# linemixer2.net
KiCad netlist of a schematic drawn in EAGLE
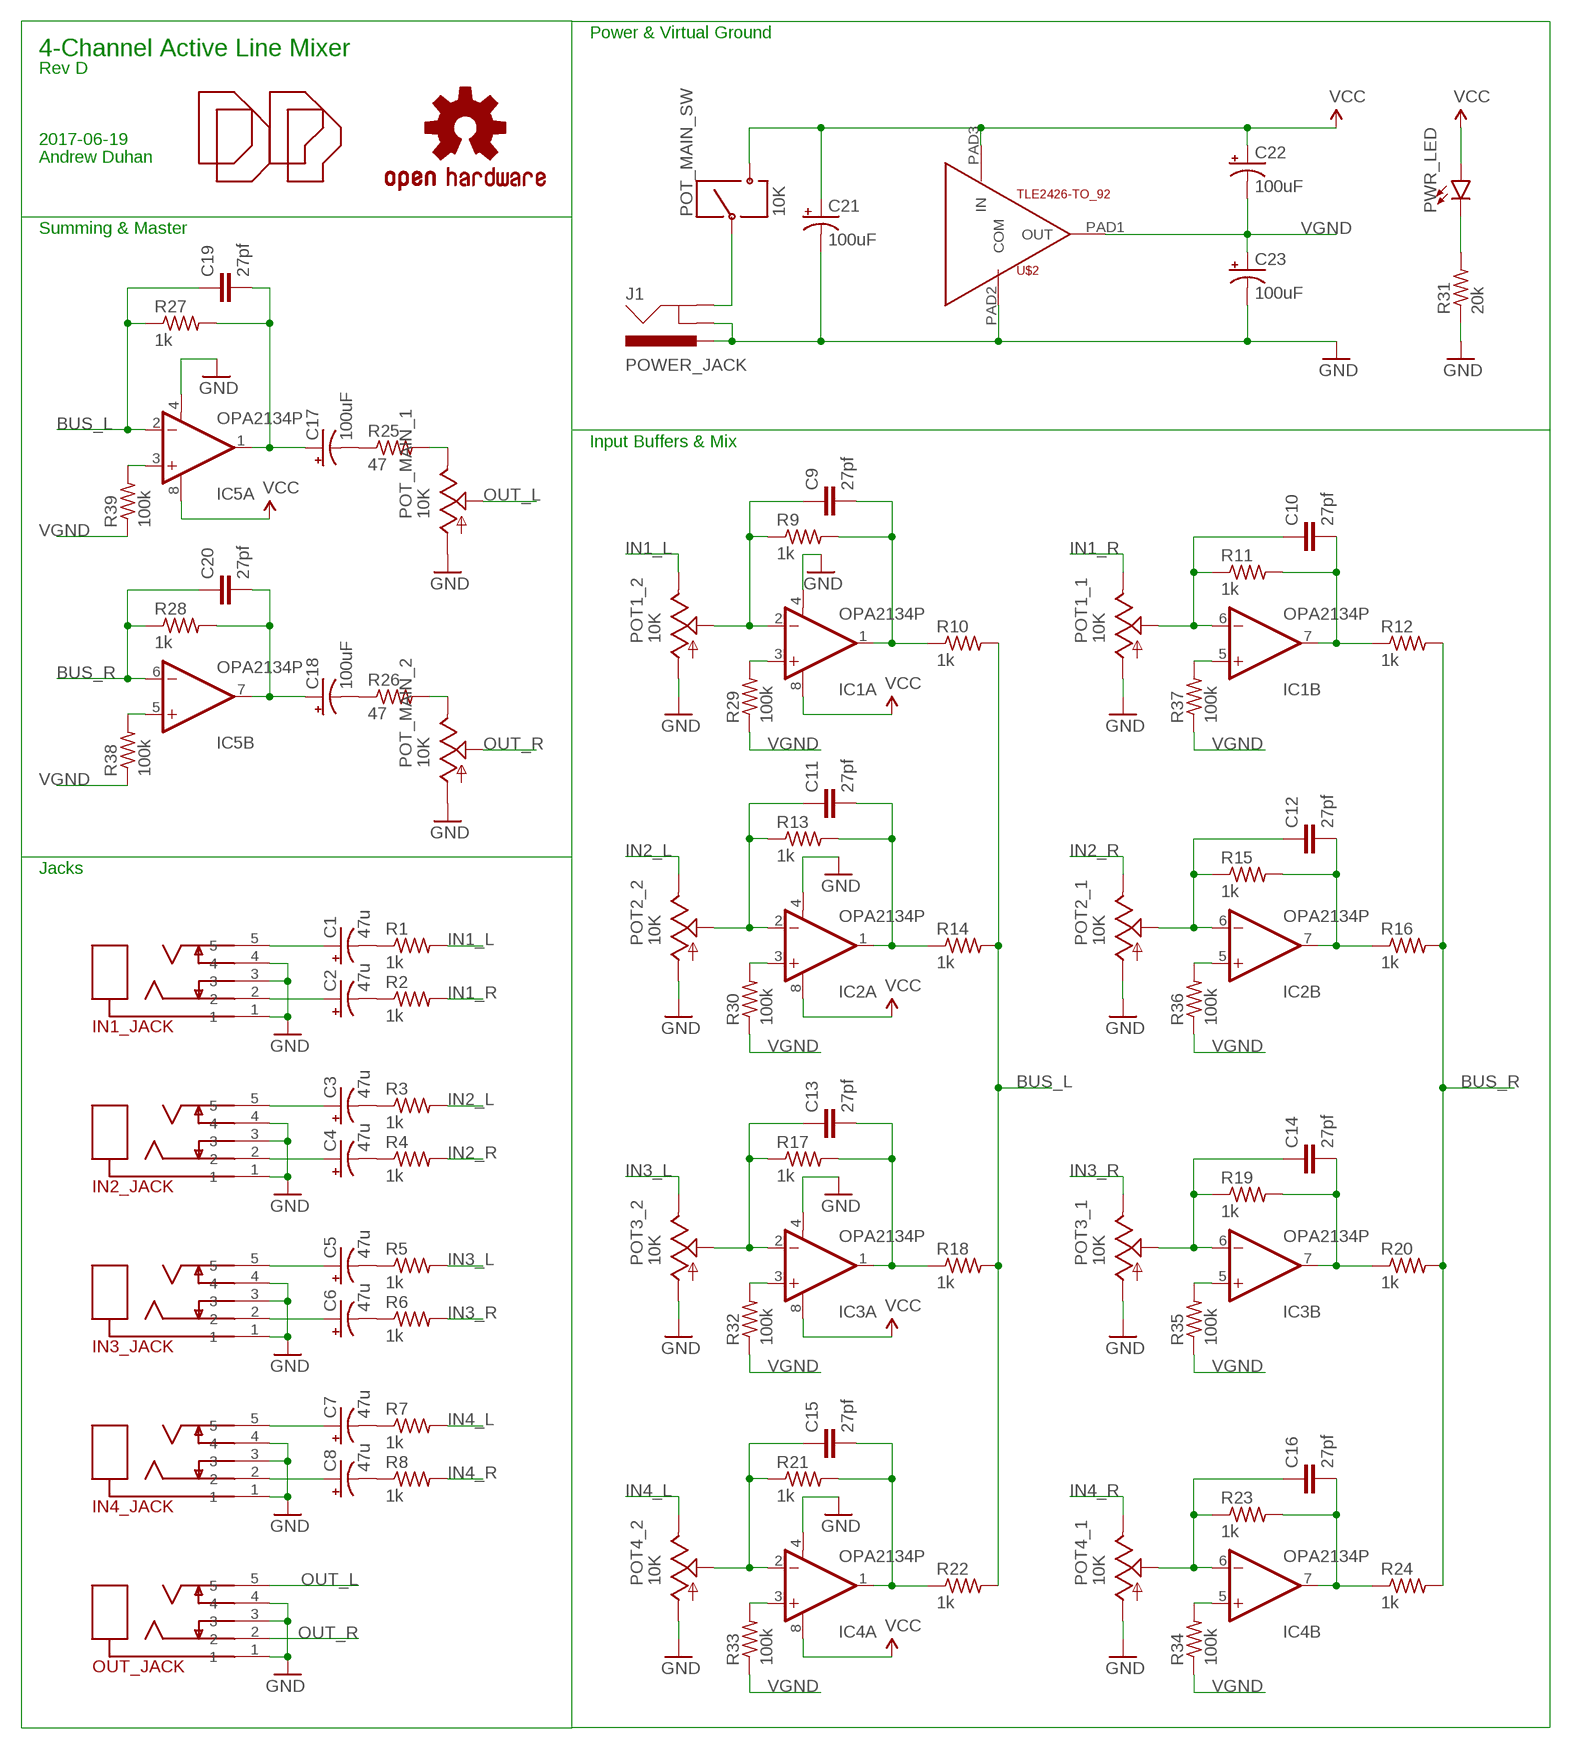
[diagram p0: schematic, sheet 1]

(export (version "E")
  (design (tool "Eeschema 10.0.6"))
  (components
    (comp (ref "C1")
      (value "47u")
      (footprint "eagle-import:CPOL-RADIAL-2.5MM-6.5MM")
      (libsource (lib "eagle-import") (part "100UF-POLAR-RADIAL-2.5MM-25V-20%"))
    )
    (comp (ref "C2")
      (value "47u")
      (footprint "eagle-import:CPOL-RADIAL-2.5MM-6.5MM")
      (libsource (lib "eagle-import") (part "100UF-POLAR-RADIAL-2.5MM-25V-20%"))
    )
    (comp (ref "C3")
      (value "47u")
      (footprint "eagle-import:CPOL-RADIAL-2.5MM-6.5MM")
      (libsource (lib "eagle-import") (part "100UF-POLAR-RADIAL-2.5MM-25V-20%"))
    )
    (comp (ref "C4")
      (value "47u")
      (footprint "eagle-import:CPOL-RADIAL-2.5MM-6.5MM")
      (libsource (lib "eagle-import") (part "100UF-POLAR-RADIAL-2.5MM-25V-20%"))
    )
    (comp (ref "C5")
      (value "47u")
      (footprint "eagle-import:CPOL-RADIAL-2.5MM-6.5MM")
      (libsource (lib "eagle-import") (part "100UF-POLAR-RADIAL-2.5MM-25V-20%"))
    )
    (comp (ref "C6")
      (value "47u")
      (footprint "eagle-import:CPOL-RADIAL-2.5MM-6.5MM")
      (libsource (lib "eagle-import") (part "100UF-POLAR-RADIAL-2.5MM-25V-20%"))
    )
    (comp (ref "C7")
      (value "47u")
      (footprint "eagle-import:CPOL-RADIAL-2.5MM-6.5MM")
      (libsource (lib "eagle-import") (part "100UF-POLAR-RADIAL-2.5MM-25V-20%"))
    )
    (comp (ref "C8")
      (value "47u")
      (footprint "eagle-import:CPOL-RADIAL-2.5MM-6.5MM")
      (libsource (lib "eagle-import") (part "100UF-POLAR-RADIAL-2.5MM-25V-20%"))
    )
    (comp (ref "C9")
      (value "27pf")
      (footprint "eagle-import:CAP-PTH-SMALL")
      (libsource (lib "eagle-import") (part "CAPPTH"))
    )
    (comp (ref "C10")
      (value "27pf")
      (footprint "eagle-import:CAP-PTH-SMALL")
      (libsource (lib "eagle-import") (part "CAPPTH"))
    )
    (comp (ref "C11")
      (value "27pf")
      (footprint "eagle-import:CAP-PTH-SMALL")
      (libsource (lib "eagle-import") (part "CAPPTH"))
    )
    (comp (ref "C12")
      (value "27pf")
      (footprint "eagle-import:CAP-PTH-SMALL")
      (libsource (lib "eagle-import") (part "CAPPTH"))
    )
    (comp (ref "C13")
      (value "27pf")
      (footprint "eagle-import:CAP-PTH-SMALL")
      (libsource (lib "eagle-import") (part "CAPPTH"))
    )
    (comp (ref "C14")
      (value "27pf")
      (footprint "eagle-import:CAP-PTH-SMALL")
      (libsource (lib "eagle-import") (part "CAPPTH"))
    )
    (comp (ref "C15")
      (value "27pf")
      (footprint "eagle-import:CAP-PTH-SMALL")
      (libsource (lib "eagle-import") (part "CAPPTH"))
    )
    (comp (ref "C16")
      (value "27pf")
      (footprint "eagle-import:CAP-PTH-SMALL")
      (libsource (lib "eagle-import") (part "CAPPTH"))
    )
    (comp (ref "C17")
      (value "100uF")
      (footprint "eagle-import:CPOL-RADIAL-2.5MM-6.5MM")
      (libsource (lib "eagle-import") (part "100UF-POLAR-RADIAL-2.5MM-25V-20%"))
    )
    (comp (ref "C18")
      (value "100uF")
      (footprint "eagle-import:CPOL-RADIAL-2.5MM-6.5MM")
      (libsource (lib "eagle-import") (part "100UF-POLAR-RADIAL-2.5MM-25V-20%"))
    )
    (comp (ref "C19")
      (value "27pf")
      (footprint "eagle-import:CAP-PTH-SMALL")
      (libsource (lib "eagle-import") (part "CAPPTH"))
    )
    (comp (ref "C20")
      (value "27pf")
      (footprint "eagle-import:CAP-PTH-SMALL")
      (libsource (lib "eagle-import") (part "CAPPTH"))
    )
    (comp (ref "C21")
      (value "100uF")
      (footprint "eagle-import:CPOL-RADIAL-2.5MM-6.5MM")
      (libsource (lib "eagle-import") (part "100UF-POLAR-RADIAL-2.5MM-25V-20%"))
    )
    (comp (ref "C22")
      (value "100uF")
      (footprint "eagle-import:CPOL-RADIAL-2.5MM-6.5MM")
      (libsource (lib "eagle-import") (part "100UF-POLAR-RADIAL-2.5MM-25V-20%"))
    )
    (comp (ref "C23")
      (value "100uF")
      (footprint "eagle-import:CPOL-RADIAL-2.5MM-6.5MM")
      (libsource (lib "eagle-import") (part "100UF-POLAR-RADIAL-2.5MM-25V-20%"))
    )
    (comp (ref "IC1")
      (value "OPA2134P")
      (footprint "eagle-import:DIL08")
      (fields (field (name "MF") "TEXAS INSTRUMENTS") (field (name "MPN") "OPA2134PA"))
      (libsource (lib "eagle-import") (part "OPA2134P"))
    )
    (comp (ref "IC2")
      (value "OPA2134P")
      (footprint "eagle-import:DIL08")
      (fields (field (name "MF") "TEXAS INSTRUMENTS") (field (name "MPN") "OPA2134PA"))
      (libsource (lib "eagle-import") (part "OPA2134P"))
    )
    (comp (ref "IC3")
      (value "OPA2134P")
      (footprint "eagle-import:DIL08")
      (fields (field (name "MF") "TEXAS INSTRUMENTS") (field (name "MPN") "OPA2134PA"))
      (libsource (lib "eagle-import") (part "OPA2134P"))
    )
    (comp (ref "IC4")
      (value "OPA2134P")
      (footprint "eagle-import:DIL08")
      (fields (field (name "MF") "TEXAS INSTRUMENTS") (field (name "MPN") "OPA2134PA"))
      (libsource (lib "eagle-import") (part "OPA2134P"))
    )
    (comp (ref "IC5")
      (value "OPA2134P")
      (footprint "eagle-import:DIL08")
      (fields (field (name "MF") "TEXAS INSTRUMENTS") (field (name "MPN") "OPA2134PA"))
      (libsource (lib "eagle-import") (part "OPA2134P"))
    )
    (comp (ref "IN1_JACK")
      (value "JACK_STEREO_SWCUI-SJ1-351X")
      (footprint "eagle-import:AUDIO_JACK-CUI-SJ1-351X")
      (libsource (lib "eagle-import") (part "JACK_STEREO_SWCUI-SJ1-351X"))
    )
    (comp (ref "IN2_JACK")
      (value "JACK_STEREO_SWCUI-SJ1-351X")
      (footprint "eagle-import:AUDIO_JACK-CUI-SJ1-351X")
      (libsource (lib "eagle-import") (part "JACK_STEREO_SWCUI-SJ1-351X"))
    )
    (comp (ref "IN3_JACK")
      (value "JACK_STEREO_SWCUI-SJ1-351X")
      (footprint "eagle-import:AUDIO_JACK-CUI-SJ1-351X")
      (libsource (lib "eagle-import") (part "JACK_STEREO_SWCUI-SJ1-351X"))
    )
    (comp (ref "IN4_JACK")
      (value "JACK_STEREO_SWCUI-SJ1-351X")
      (footprint "eagle-import:AUDIO_JACK-CUI-SJ1-351X")
      (libsource (lib "eagle-import") (part "JACK_STEREO_SWCUI-SJ1-351X"))
    )
    (comp (ref "J1")
      (value "POWER_JACK")
      (footprint "eagle-import:POWER_JACK_PTH")
      (libsource (lib "eagle-import") (part "POWER_JACK"))
    )
    (comp (ref "LOGO1")
      (value "OSHW-LOGOS")
      (footprint "eagle-import:OSHW-LOGO-S")
      (libsource (lib "eagle-import") (part "OSHW-LOGOS"))
    )
    (comp (ref "OUT_JACK")
      (value "JACK_STEREO_SWCUI-SJ1-351X")
      (footprint "eagle-import:AUDIO_JACK-CUI-SJ1-351X")
      (libsource (lib "eagle-import") (part "JACK_STEREO_SWCUI-SJ1-351X"))
    )
    (comp (ref "POT1_")
      (value "10K")
      (footprint "eagle-import:BOURNS_PTD902")
      (libsource (lib "eagle-import") (part "POT_BOURNS_PTD902"))
    )
    (comp (ref "POT2_")
      (value "10K")
      (footprint "eagle-import:BOURNS_PTD902")
      (libsource (lib "eagle-import") (part "POT_BOURNS_PTD902"))
    )
    (comp (ref "POT3_")
      (value "10K")
      (footprint "eagle-import:BOURNS_PTD902")
      (libsource (lib "eagle-import") (part "POT_BOURNS_PTD902"))
    )
    (comp (ref "POT4_")
      (value "10K")
      (footprint "eagle-import:BOURNS_PTD902")
      (libsource (lib "eagle-import") (part "POT_BOURNS_PTD902"))
    )
    (comp (ref "POT_MAIN_")
      (value "10K")
      (footprint "eagle-import:BOURNS_PTR902")
      (libsource (lib "eagle-import") (part "POT_BOURNS_PTR902"))
    )
    (comp (ref "PWR_LED")
      (value "LED3MM")
      (footprint "eagle-import:LED_3MM")
      (libsource (lib "eagle-import") (part "LED3MM"))
    )
    (comp (ref "R1")
      (value "1k")
      (footprint "eagle-import:0204_5")
      (libsource (lib "eagle-import") (part "R-US_0204/5"))
    )
    (comp (ref "R2")
      (value "1k")
      (footprint "eagle-import:0204_5")
      (libsource (lib "eagle-import") (part "R-US_0204/5"))
    )
    (comp (ref "R3")
      (value "1k")
      (footprint "eagle-import:0204_5")
      (libsource (lib "eagle-import") (part "R-US_0204/5"))
    )
    (comp (ref "R4")
      (value "1k")
      (footprint "eagle-import:0204_5")
      (libsource (lib "eagle-import") (part "R-US_0204/5"))
    )
    (comp (ref "R5")
      (value "1k")
      (footprint "eagle-import:0204_5")
      (libsource (lib "eagle-import") (part "R-US_0204/5"))
    )
    (comp (ref "R6")
      (value "1k")
      (footprint "eagle-import:0204_5")
      (libsource (lib "eagle-import") (part "R-US_0204/5"))
    )
    (comp (ref "R7")
      (value "1k")
      (footprint "eagle-import:0204_5")
      (libsource (lib "eagle-import") (part "R-US_0204/5"))
    )
    (comp (ref "R8")
      (value "1k")
      (footprint "eagle-import:0204_5")
      (libsource (lib "eagle-import") (part "R-US_0204/5"))
    )
    (comp (ref "R9")
      (value "1k")
      (footprint "eagle-import:0204_5")
      (libsource (lib "eagle-import") (part "R-US_0204/5"))
    )
    (comp (ref "R10")
      (value "1k")
      (footprint "eagle-import:0204_5")
      (libsource (lib "eagle-import") (part "R-US_0204/5"))
    )
    (comp (ref "R11")
      (value "1k")
      (footprint "eagle-import:0204_5")
      (libsource (lib "eagle-import") (part "R-US_0204/5"))
    )
    (comp (ref "R12")
      (value "1k")
      (footprint "eagle-import:0204_5")
      (libsource (lib "eagle-import") (part "R-US_0204/5"))
    )
    (comp (ref "R13")
      (value "1k")
      (footprint "eagle-import:0204_5")
      (libsource (lib "eagle-import") (part "R-US_0204/5"))
    )
    (comp (ref "R14")
      (value "1k")
      (footprint "eagle-import:0204_5")
      (libsource (lib "eagle-import") (part "R-US_0204/5"))
    )
    (comp (ref "R15")
      (value "1k")
      (footprint "eagle-import:0204_5")
      (libsource (lib "eagle-import") (part "R-US_0204/5"))
    )
    (comp (ref "R16")
      (value "1k")
      (footprint "eagle-import:0204_5")
      (libsource (lib "eagle-import") (part "R-US_0204/5"))
    )
    (comp (ref "R17")
      (value "1k")
      (footprint "eagle-import:0204_5")
      (libsource (lib "eagle-import") (part "R-US_0204/5"))
    )
    (comp (ref "R18")
      (value "1k")
      (footprint "eagle-import:0204_5")
      (libsource (lib "eagle-import") (part "R-US_0204/5"))
    )
    (comp (ref "R19")
      (value "1k")
      (footprint "eagle-import:0204_5")
      (libsource (lib "eagle-import") (part "R-US_0204/5"))
    )
    (comp (ref "R20")
      (value "1k")
      (footprint "eagle-import:0204_5")
      (libsource (lib "eagle-import") (part "R-US_0204/5"))
    )
    (comp (ref "R21")
      (value "1k")
      (footprint "eagle-import:0204_5")
      (libsource (lib "eagle-import") (part "R-US_0204/5"))
    )
    (comp (ref "R22")
      (value "1k")
      (footprint "eagle-import:0204_5")
      (libsource (lib "eagle-import") (part "R-US_0204/5"))
    )
    (comp (ref "R23")
      (value "1k")
      (footprint "eagle-import:0204_5")
      (libsource (lib "eagle-import") (part "R-US_0204/5"))
    )
    (comp (ref "R24")
      (value "1k")
      (footprint "eagle-import:0204_5")
      (libsource (lib "eagle-import") (part "R-US_0204/5"))
    )
    (comp (ref "R25")
      (value "47")
      (footprint "eagle-import:0204_5")
      (libsource (lib "eagle-import") (part "R-US_0204/5"))
    )
    (comp (ref "R26")
      (value "47")
      (footprint "eagle-import:0204_5")
      (libsource (lib "eagle-import") (part "R-US_0204/5"))
    )
    (comp (ref "R27")
      (value "1k")
      (footprint "eagle-import:0204_5")
      (libsource (lib "eagle-import") (part "R-US_0204/5"))
    )
    (comp (ref "R28")
      (value "1k")
      (footprint "eagle-import:0204_5")
      (libsource (lib "eagle-import") (part "R-US_0204/5"))
    )
    (comp (ref "R29")
      (value "100k")
      (footprint "eagle-import:0204_5")
      (libsource (lib "eagle-import") (part "R-US_0204/5"))
    )
    (comp (ref "R30")
      (value "100k")
      (footprint "eagle-import:0204_5")
      (libsource (lib "eagle-import") (part "R-US_0204/5"))
    )
    (comp (ref "R31")
      (value "20k")
      (footprint "eagle-import:0204_5")
      (libsource (lib "eagle-import") (part "R-US_0204/5"))
    )
    (comp (ref "R32")
      (value "100k")
      (footprint "eagle-import:0204_5")
      (libsource (lib "eagle-import") (part "R-US_0204/5"))
    )
    (comp (ref "R33")
      (value "100k")
      (footprint "eagle-import:0204_5")
      (libsource (lib "eagle-import") (part "R-US_0204/5"))
    )
    (comp (ref "R34")
      (value "100k")
      (footprint "eagle-import:0204_5")
      (libsource (lib "eagle-import") (part "R-US_0204/5"))
    )
    (comp (ref "R35")
      (value "100k")
      (footprint "eagle-import:0204_5")
      (libsource (lib "eagle-import") (part "R-US_0204/5"))
    )
    (comp (ref "R36")
      (value "100k")
      (footprint "eagle-import:0204_5")
      (libsource (lib "eagle-import") (part "R-US_0204/5"))
    )
    (comp (ref "R37")
      (value "100k")
      (footprint "eagle-import:0204_5")
      (libsource (lib "eagle-import") (part "R-US_0204/5"))
    )
    (comp (ref "R38")
      (value "100k")
      (footprint "eagle-import:0204_5")
      (libsource (lib "eagle-import") (part "R-US_0204/5"))
    )
    (comp (ref "R39")
      (value "100k")
      (footprint "eagle-import:0204_5")
      (libsource (lib "eagle-import") (part "R-US_0204/5"))
    )
    (comp (ref "U$1")
      (value "DP_LOGO")
      (footprint "eagle-import:DP_LOGO")
      (libsource (lib "eagle-import") (part "DP_LOGO"))
    )
    (comp (ref "U$2")
      (value "TLE2426-TO_92")
      (footprint "eagle-import:TO-92")
      (libsource (lib "eagle-import") (part "TLE2426-TO_92"))
    )
    (comp (ref "U$3")
      (value "DP_LOGO")
      (footprint "eagle-import:DP_LOGO")
      (libsource (lib "eagle-import") (part "DP_LOGO"))
    )
  )
  (nets
    (net (code "1") (name "/BUS_L") (class "Default")
      (node (ref "C19") (pin "1") (pinfunction "1_1") (pintype "passive"))
      (node (ref "IC5") (pin "2") (pinfunction "-IN_2") (pintype "input"))
      (node (ref "R10") (pin "2") (pinfunction "2_2") (pintype "passive"))
      (node (ref "R14") (pin "2") (pinfunction "2_2") (pintype "passive"))
      (node (ref "R18") (pin "2") (pinfunction "2_2") (pintype "passive"))
      (node (ref "R22") (pin "2") (pinfunction "2_2") (pintype "passive"))
      (node (ref "R27") (pin "1") (pinfunction "1_1") (pintype "passive"))
    )
    (net (code "2") (name "/BUS_R") (class "Default")
      (node (ref "C20") (pin "1") (pinfunction "1_1") (pintype "passive"))
      (node (ref "IC5") (pin "6") (pinfunction "-IN_6") (pintype "input"))
      (node (ref "R12") (pin "2") (pinfunction "2_2") (pintype "passive"))
      (node (ref "R16") (pin "2") (pinfunction "2_2") (pintype "passive"))
      (node (ref "R20") (pin "2") (pinfunction "2_2") (pintype "passive"))
      (node (ref "R24") (pin "2") (pinfunction "2_2") (pintype "passive"))
      (node (ref "R28") (pin "1") (pinfunction "1_1") (pintype "passive"))
    )
    (net (code "3") (name "/IN1_L") (class "Default")
      (node (ref "POT1_") (pin "R2-B") (pinfunction "B_R2-B") (pintype "passive"))
      (node (ref "R1") (pin "2") (pinfunction "2_2") (pintype "passive"))
    )
    (net (code "4") (name "/IN1_R") (class "Default")
      (node (ref "POT1_") (pin "R1-B") (pinfunction "B_R1-B") (pintype "passive"))
      (node (ref "R2") (pin "2") (pinfunction "2_2") (pintype "passive"))
    )
    (net (code "5") (name "/IN2_L") (class "Default")
      (node (ref "POT2_") (pin "R2-B") (pinfunction "B_R2-B") (pintype "passive"))
      (node (ref "R3") (pin "2") (pinfunction "2_2") (pintype "passive"))
    )
    (net (code "6") (name "/IN2_R") (class "Default")
      (node (ref "POT2_") (pin "R1-B") (pinfunction "B_R1-B") (pintype "passive"))
      (node (ref "R4") (pin "2") (pinfunction "2_2") (pintype "passive"))
    )
    (net (code "7") (name "/IN3_L") (class "Default")
      (node (ref "POT3_") (pin "R2-B") (pinfunction "B_R2-B") (pintype "passive"))
      (node (ref "R5") (pin "2") (pinfunction "2_2") (pintype "passive"))
    )
    (net (code "8") (name "/IN3_R") (class "Default")
      (node (ref "POT3_") (pin "R1-B") (pinfunction "B_R1-B") (pintype "passive"))
      (node (ref "R6") (pin "2") (pinfunction "2_2") (pintype "passive"))
    )
    (net (code "9") (name "/IN4_L") (class "Default")
      (node (ref "POT4_") (pin "R2-B") (pinfunction "B_R2-B") (pintype "passive"))
      (node (ref "R7") (pin "2") (pinfunction "2_2") (pintype "passive"))
    )
    (net (code "10") (name "/IN4_R") (class "Default")
      (node (ref "POT4_") (pin "R1-B") (pinfunction "B_R1-B") (pintype "passive"))
      (node (ref "R8") (pin "2") (pinfunction "2_2") (pintype "passive"))
    )
    (net (code "11") (name "/OUT_L") (class "Default")
      (node (ref "OUT_JACK") (pin "5") (pinfunction "5_5") (pintype "bidirectional"))
      (node (ref "POT_MAIN_") (pin "R1-W") (pinfunction "W_R1-W") (pintype "passive"))
    )
    (net (code "12") (name "/OUT_R") (class "Default")
      (node (ref "OUT_JACK") (pin "2") (pinfunction "2_2") (pintype "bidirectional"))
      (node (ref "POT_MAIN_") (pin "R2-W") (pinfunction "W_R2-W") (pintype "passive"))
    )
    (net (code "13") (name "/VGND") (class "Default")
      (node (ref "C22") (pin "2") (pinfunction "-_2") (pintype "passive"))
      (node (ref "C23") (pin "1") (pinfunction "+_1") (pintype "passive"))
      (node (ref "R29") (pin "1") (pinfunction "1_1") (pintype "passive"))
      (node (ref "R30") (pin "1") (pinfunction "1_1") (pintype "passive"))
      (node (ref "R32") (pin "1") (pinfunction "1_1") (pintype "passive"))
      (node (ref "R33") (pin "1") (pinfunction "1_1") (pintype "passive"))
      (node (ref "R34") (pin "1") (pinfunction "1_1") (pintype "passive"))
      (node (ref "R35") (pin "1") (pinfunction "1_1") (pintype "passive"))
      (node (ref "R36") (pin "1") (pinfunction "1_1") (pintype "passive"))
      (node (ref "R37") (pin "1") (pinfunction "1_1") (pintype "passive"))
      (node (ref "R38") (pin "1") (pinfunction "1_1") (pintype "passive"))
      (node (ref "R39") (pin "1") (pinfunction "1_1") (pintype "passive"))
      (node (ref "U$2") (pin "PAD1") (pinfunction "OUT_PAD1") (pintype "bidirectional"))
    )
    (net (code "14") (name "GND") (class "Default")
      (node (ref "C21") (pin "2") (pinfunction "-_2") (pintype "passive"))
      (node (ref "C23") (pin "2") (pinfunction "-_2") (pintype "passive"))
      (node (ref "IC1") (pin "4") (pinfunction "V-_4") (pintype "power_in"))
      (node (ref "IC2") (pin "4") (pinfunction "V-_4") (pintype "power_in"))
      (node (ref "IC3") (pin "4") (pinfunction "V-_4") (pintype "power_in"))
      (node (ref "IC4") (pin "4") (pinfunction "V-_4") (pintype "power_in"))
      (node (ref "IC5") (pin "4") (pinfunction "V-_4") (pintype "power_in"))
      (node (ref "IN1_JACK") (pin "1") (pinfunction "1_1") (pintype "bidirectional"))
      (node (ref "IN1_JACK") (pin "3") (pinfunction "3_3") (pintype "bidirectional"))
      (node (ref "IN1_JACK") (pin "4") (pinfunction "4_4") (pintype "bidirectional"))
      (node (ref "IN2_JACK") (pin "1") (pinfunction "1_1") (pintype "bidirectional"))
      (node (ref "IN2_JACK") (pin "3") (pinfunction "3_3") (pintype "bidirectional"))
      (node (ref "IN2_JACK") (pin "4") (pinfunction "4_4") (pintype "bidirectional"))
      (node (ref "IN3_JACK") (pin "1") (pinfunction "1_1") (pintype "bidirectional"))
      (node (ref "IN3_JACK") (pin "3") (pinfunction "3_3") (pintype "bidirectional"))
      (node (ref "IN3_JACK") (pin "4") (pinfunction "4_4") (pintype "bidirectional"))
      (node (ref "IN4_JACK") (pin "1") (pinfunction "1_1") (pintype "bidirectional"))
      (node (ref "IN4_JACK") (pin "3") (pinfunction "3_3") (pintype "bidirectional"))
      (node (ref "IN4_JACK") (pin "4") (pinfunction "4_4") (pintype "bidirectional"))
      (node (ref "J1") (pin "GNDBREAK") (pinfunction "GNDBREAK_GNDBREAK") (pintype "bidirectional"))
      (node (ref "J1") (pin "PWR") (pinfunction "PWR_PWR") (pintype "bidirectional"))
      (node (ref "OUT_JACK") (pin "1") (pinfunction "1_1") (pintype "bidirectional"))
      (node (ref "OUT_JACK") (pin "3") (pinfunction "3_3") (pintype "bidirectional"))
      (node (ref "OUT_JACK") (pin "4") (pinfunction "4_4") (pintype "bidirectional"))
      (node (ref "POT1_") (pin "R1-A") (pinfunction "A_R1-A") (pintype "passive"))
      (node (ref "POT1_") (pin "R2-A") (pinfunction "A_R2-A") (pintype "passive"))
      (node (ref "POT2_") (pin "R1-A") (pinfunction "A_R1-A") (pintype "passive"))
      (node (ref "POT2_") (pin "R2-A") (pinfunction "A_R2-A") (pintype "passive"))
      (node (ref "POT3_") (pin "R1-A") (pinfunction "A_R1-A") (pintype "passive"))
      (node (ref "POT3_") (pin "R2-A") (pinfunction "A_R2-A") (pintype "passive"))
      (node (ref "POT4_") (pin "R1-A") (pinfunction "A_R1-A") (pintype "passive"))
      (node (ref "POT4_") (pin "R2-A") (pinfunction "A_R2-A") (pintype "passive"))
      (node (ref "POT_MAIN_") (pin "R1-A") (pinfunction "A_R1-A") (pintype "passive"))
      (node (ref "POT_MAIN_") (pin "R2-A") (pinfunction "A_R2-A") (pintype "passive"))
      (node (ref "R31") (pin "1") (pinfunction "1_1") (pintype "passive"))
      (node (ref "U$2") (pin "PAD2") (pinfunction "COM_PAD2") (pintype "bidirectional"))
    )
    (net (code "15") (name "Net-(C1-+)") (class "Default")
      (node (ref "C1") (pin "1") (pinfunction "+_1") (pintype "passive"))
      (node (ref "IN1_JACK") (pin "5") (pinfunction "5_5") (pintype "bidirectional"))
    )
    (net (code "16") (name "Net-(C1--)") (class "Default")
      (node (ref "C1") (pin "2") (pinfunction "-_2") (pintype "passive"))
      (node (ref "R1") (pin "1") (pinfunction "1_1") (pintype "passive"))
    )
    (net (code "17") (name "Net-(C2-+)") (class "Default")
      (node (ref "C2") (pin "1") (pinfunction "+_1") (pintype "passive"))
      (node (ref "IN1_JACK") (pin "2") (pinfunction "2_2") (pintype "bidirectional"))
    )
    (net (code "18") (name "Net-(C2--)") (class "Default")
      (node (ref "C2") (pin "2") (pinfunction "-_2") (pintype "passive"))
      (node (ref "R2") (pin "1") (pinfunction "1_1") (pintype "passive"))
    )
    (net (code "19") (name "Net-(C3-+)") (class "Default")
      (node (ref "C3") (pin "1") (pinfunction "+_1") (pintype "passive"))
      (node (ref "IN2_JACK") (pin "5") (pinfunction "5_5") (pintype "bidirectional"))
    )
    (net (code "20") (name "Net-(C3--)") (class "Default")
      (node (ref "C3") (pin "2") (pinfunction "-_2") (pintype "passive"))
      (node (ref "R3") (pin "1") (pinfunction "1_1") (pintype "passive"))
    )
    (net (code "21") (name "Net-(C4-+)") (class "Default")
      (node (ref "C4") (pin "1") (pinfunction "+_1") (pintype "passive"))
      (node (ref "IN2_JACK") (pin "2") (pinfunction "2_2") (pintype "bidirectional"))
    )
    (net (code "22") (name "Net-(C4--)") (class "Default")
      (node (ref "C4") (pin "2") (pinfunction "-_2") (pintype "passive"))
      (node (ref "R4") (pin "1") (pinfunction "1_1") (pintype "passive"))
    )
    (net (code "23") (name "Net-(C5-+)") (class "Default")
      (node (ref "C5") (pin "1") (pinfunction "+_1") (pintype "passive"))
      (node (ref "IN3_JACK") (pin "5") (pinfunction "5_5") (pintype "bidirectional"))
    )
    (net (code "24") (name "Net-(C5--)") (class "Default")
      (node (ref "C5") (pin "2") (pinfunction "-_2") (pintype "passive"))
      (node (ref "R5") (pin "1") (pinfunction "1_1") (pintype "passive"))
    )
    (net (code "25") (name "Net-(C6-+)") (class "Default")
      (node (ref "C6") (pin "1") (pinfunction "+_1") (pintype "passive"))
      (node (ref "IN3_JACK") (pin "2") (pinfunction "2_2") (pintype "bidirectional"))
    )
    (net (code "26") (name "Net-(C6--)") (class "Default")
      (node (ref "C6") (pin "2") (pinfunction "-_2") (pintype "passive"))
      (node (ref "R6") (pin "1") (pinfunction "1_1") (pintype "passive"))
    )
    (net (code "27") (name "Net-(C7-+)") (class "Default")
      (node (ref "C7") (pin "1") (pinfunction "+_1") (pintype "passive"))
      (node (ref "IN4_JACK") (pin "5") (pinfunction "5_5") (pintype "bidirectional"))
    )
    (net (code "28") (name "Net-(C7--)") (class "Default")
      (node (ref "C7") (pin "2") (pinfunction "-_2") (pintype "passive"))
      (node (ref "R7") (pin "1") (pinfunction "1_1") (pintype "passive"))
    )
    (net (code "29") (name "Net-(C8-+)") (class "Default")
      (node (ref "C8") (pin "1") (pinfunction "+_1") (pintype "passive"))
      (node (ref "IN4_JACK") (pin "2") (pinfunction "2_2") (pintype "bidirectional"))
    )
    (net (code "30") (name "Net-(C8--)") (class "Default")
      (node (ref "C8") (pin "2") (pinfunction "-_2") (pintype "passive"))
      (node (ref "R8") (pin "1") (pinfunction "1_1") (pintype "passive"))
    )
    (net (code "31") (name "Net-(C17-+)") (class "Default")
      (node (ref "C17") (pin "1") (pinfunction "+_1") (pintype "passive"))
      (node (ref "C19") (pin "2") (pinfunction "2_2") (pintype "passive"))
      (node (ref "IC5") (pin "1") (pinfunction "OUT_1") (pintype "output"))
      (node (ref "R27") (pin "2") (pinfunction "2_2") (pintype "passive"))
    )
    (net (code "32") (name "Net-(C17--)") (class "Default")
      (node (ref "C17") (pin "2") (pinfunction "-_2") (pintype "passive"))
      (node (ref "R25") (pin "1") (pinfunction "1_1") (pintype "passive"))
    )
    (net (code "33") (name "Net-(C18-+)") (class "Default")
      (node (ref "C18") (pin "1") (pinfunction "+_1") (pintype "passive"))
      (node (ref "C20") (pin "2") (pinfunction "2_2") (pintype "passive"))
      (node (ref "IC5") (pin "7") (pinfunction "OUT_7") (pintype "output"))
      (node (ref "R28") (pin "2") (pinfunction "2_2") (pintype "passive"))
    )
    (net (code "34") (name "Net-(C18--)") (class "Default")
      (node (ref "C18") (pin "2") (pinfunction "-_2") (pintype "passive"))
      (node (ref "R26") (pin "1") (pinfunction "1_1") (pintype "passive"))
    )
    (net (code "35") (name "Net-(IC1A-+IN)") (class "Default")
      (node (ref "IC1") (pin "3") (pinfunction "+IN_3") (pintype "input"))
      (node (ref "R29") (pin "2") (pinfunction "2_2") (pintype "passive"))
    )
    (net (code "36") (name "Net-(IC1A--IN)") (class "Default")
      (node (ref "C9") (pin "1") (pinfunction "1_1") (pintype "passive"))
      (node (ref "IC1") (pin "2") (pinfunction "-IN_2") (pintype "input"))
      (node (ref "POT1_") (pin "R2-W") (pinfunction "W_R2-W") (pintype "passive"))
      (node (ref "R9") (pin "1") (pinfunction "1_1") (pintype "passive"))
    )
    (net (code "37") (name "Net-(IC1A-OUT)") (class "Default")
      (node (ref "C9") (pin "2") (pinfunction "2_2") (pintype "passive"))
      (node (ref "IC1") (pin "1") (pinfunction "OUT_1") (pintype "output"))
      (node (ref "R10") (pin "1") (pinfunction "1_1") (pintype "passive"))
      (node (ref "R9") (pin "2") (pinfunction "2_2") (pintype "passive"))
    )
    (net (code "38") (name "Net-(IC1B-+IN)") (class "Default")
      (node (ref "IC1") (pin "5") (pinfunction "+IN_5") (pintype "input"))
      (node (ref "R37") (pin "2") (pinfunction "2_2") (pintype "passive"))
    )
    (net (code "39") (name "Net-(IC1B--IN)") (class "Default")
      (node (ref "C10") (pin "1") (pinfunction "1_1") (pintype "passive"))
      (node (ref "IC1") (pin "6") (pinfunction "-IN_6") (pintype "input"))
      (node (ref "POT1_") (pin "R1-W") (pinfunction "W_R1-W") (pintype "passive"))
      (node (ref "R11") (pin "1") (pinfunction "1_1") (pintype "passive"))
    )
    (net (code "40") (name "Net-(IC1B-OUT)") (class "Default")
      (node (ref "C10") (pin "2") (pinfunction "2_2") (pintype "passive"))
      (node (ref "IC1") (pin "7") (pinfunction "OUT_7") (pintype "output"))
      (node (ref "R11") (pin "2") (pinfunction "2_2") (pintype "passive"))
      (node (ref "R12") (pin "1") (pinfunction "1_1") (pintype "passive"))
    )
    (net (code "41") (name "Net-(IC2A-+IN)") (class "Default")
      (node (ref "IC2") (pin "3") (pinfunction "+IN_3") (pintype "input"))
      (node (ref "R30") (pin "2") (pinfunction "2_2") (pintype "passive"))
    )
    (net (code "42") (name "Net-(IC2A--IN)") (class "Default")
      (node (ref "C11") (pin "1") (pinfunction "1_1") (pintype "passive"))
      (node (ref "IC2") (pin "2") (pinfunction "-IN_2") (pintype "input"))
      (node (ref "POT2_") (pin "R2-W") (pinfunction "W_R2-W") (pintype "passive"))
      (node (ref "R13") (pin "1") (pinfunction "1_1") (pintype "passive"))
    )
    (net (code "43") (name "Net-(IC2A-OUT)") (class "Default")
      (node (ref "C11") (pin "2") (pinfunction "2_2") (pintype "passive"))
      (node (ref "IC2") (pin "1") (pinfunction "OUT_1") (pintype "output"))
      (node (ref "R13") (pin "2") (pinfunction "2_2") (pintype "passive"))
      (node (ref "R14") (pin "1") (pinfunction "1_1") (pintype "passive"))
    )
    (net (code "44") (name "Net-(IC2B-+IN)") (class "Default")
      (node (ref "IC2") (pin "5") (pinfunction "+IN_5") (pintype "input"))
      (node (ref "R36") (pin "2") (pinfunction "2_2") (pintype "passive"))
    )
    (net (code "45") (name "Net-(IC2B--IN)") (class "Default")
      (node (ref "C12") (pin "1") (pinfunction "1_1") (pintype "passive"))
      (node (ref "IC2") (pin "6") (pinfunction "-IN_6") (pintype "input"))
      (node (ref "POT2_") (pin "R1-W") (pinfunction "W_R1-W") (pintype "passive"))
      (node (ref "R15") (pin "1") (pinfunction "1_1") (pintype "passive"))
    )
    (net (code "46") (name "Net-(IC2B-OUT)") (class "Default")
      (node (ref "C12") (pin "2") (pinfunction "2_2") (pintype "passive"))
      (node (ref "IC2") (pin "7") (pinfunction "OUT_7") (pintype "output"))
      (node (ref "R15") (pin "2") (pinfunction "2_2") (pintype "passive"))
      (node (ref "R16") (pin "1") (pinfunction "1_1") (pintype "passive"))
    )
    (net (code "47") (name "Net-(IC3A-+IN)") (class "Default")
      (node (ref "IC3") (pin "3") (pinfunction "+IN_3") (pintype "input"))
      (node (ref "R32") (pin "2") (pinfunction "2_2") (pintype "passive"))
    )
    (net (code "48") (name "Net-(IC3A--IN)") (class "Default")
      (node (ref "C13") (pin "1") (pinfunction "1_1") (pintype "passive"))
      (node (ref "IC3") (pin "2") (pinfunction "-IN_2") (pintype "input"))
      (node (ref "POT3_") (pin "R2-W") (pinfunction "W_R2-W") (pintype "passive"))
      (node (ref "R17") (pin "1") (pinfunction "1_1") (pintype "passive"))
    )
    (net (code "49") (name "Net-(IC3A-OUT)") (class "Default")
      (node (ref "C13") (pin "2") (pinfunction "2_2") (pintype "passive"))
      (node (ref "IC3") (pin "1") (pinfunction "OUT_1") (pintype "output"))
      (node (ref "R17") (pin "2") (pinfunction "2_2") (pintype "passive"))
      (node (ref "R18") (pin "1") (pinfunction "1_1") (pintype "passive"))
    )
    (net (code "50") (name "Net-(IC3B-+IN)") (class "Default")
      (node (ref "IC3") (pin "5") (pinfunction "+IN_5") (pintype "input"))
      (node (ref "R35") (pin "2") (pinfunction "2_2") (pintype "passive"))
    )
    (net (code "51") (name "Net-(IC3B--IN)") (class "Default")
      (node (ref "C14") (pin "1") (pinfunction "1_1") (pintype "passive"))
      (node (ref "IC3") (pin "6") (pinfunction "-IN_6") (pintype "input"))
      (node (ref "POT3_") (pin "R1-W") (pinfunction "W_R1-W") (pintype "passive"))
      (node (ref "R19") (pin "1") (pinfunction "1_1") (pintype "passive"))
    )
    (net (code "52") (name "Net-(IC3B-OUT)") (class "Default")
      (node (ref "C14") (pin "2") (pinfunction "2_2") (pintype "passive"))
      (node (ref "IC3") (pin "7") (pinfunction "OUT_7") (pintype "output"))
      (node (ref "R19") (pin "2") (pinfunction "2_2") (pintype "passive"))
      (node (ref "R20") (pin "1") (pinfunction "1_1") (pintype "passive"))
    )
    (net (code "53") (name "Net-(IC4A-+IN)") (class "Default")
      (node (ref "IC4") (pin "3") (pinfunction "+IN_3") (pintype "input"))
      (node (ref "R33") (pin "2") (pinfunction "2_2") (pintype "passive"))
    )
    (net (code "54") (name "Net-(IC4A--IN)") (class "Default")
      (node (ref "C15") (pin "1") (pinfunction "1_1") (pintype "passive"))
      (node (ref "IC4") (pin "2") (pinfunction "-IN_2") (pintype "input"))
      (node (ref "POT4_") (pin "R2-W") (pinfunction "W_R2-W") (pintype "passive"))
      (node (ref "R21") (pin "1") (pinfunction "1_1") (pintype "passive"))
    )
    (net (code "55") (name "Net-(IC4A-OUT)") (class "Default")
      (node (ref "C15") (pin "2") (pinfunction "2_2") (pintype "passive"))
      (node (ref "IC4") (pin "1") (pinfunction "OUT_1") (pintype "output"))
      (node (ref "R21") (pin "2") (pinfunction "2_2") (pintype "passive"))
      (node (ref "R22") (pin "1") (pinfunction "1_1") (pintype "passive"))
    )
    (net (code "56") (name "Net-(IC4B-+IN)") (class "Default")
      (node (ref "IC4") (pin "5") (pinfunction "+IN_5") (pintype "input"))
      (node (ref "R34") (pin "2") (pinfunction "2_2") (pintype "passive"))
    )
    (net (code "57") (name "Net-(IC4B--IN)") (class "Default")
      (node (ref "C16") (pin "1") (pinfunction "1_1") (pintype "passive"))
      (node (ref "IC4") (pin "6") (pinfunction "-IN_6") (pintype "input"))
      (node (ref "POT4_") (pin "R1-W") (pinfunction "W_R1-W") (pintype "passive"))
      (node (ref "R23") (pin "1") (pinfunction "1_1") (pintype "passive"))
    )
    (net (code "58") (name "Net-(IC4B-OUT)") (class "Default")
      (node (ref "C16") (pin "2") (pinfunction "2_2") (pintype "passive"))
      (node (ref "IC4") (pin "7") (pinfunction "OUT_7") (pintype "output"))
      (node (ref "R23") (pin "2") (pinfunction "2_2") (pintype "passive"))
      (node (ref "R24") (pin "1") (pinfunction "1_1") (pintype "passive"))
    )
    (net (code "59") (name "Net-(IC5A-+IN)") (class "Default")
      (node (ref "IC5") (pin "3") (pinfunction "+IN_3") (pintype "input"))
      (node (ref "R39") (pin "2") (pinfunction "2_2") (pintype "passive"))
    )
    (net (code "60") (name "Net-(IC5B-+IN)") (class "Default")
      (node (ref "IC5") (pin "5") (pinfunction "+IN_5") (pintype "input"))
      (node (ref "R38") (pin "2") (pinfunction "2_2") (pintype "passive"))
    )
    (net (code "61") (name "Net-(POT_MAIN_A-B)") (class "Default")
      (node (ref "POT_MAIN_") (pin "R1-B") (pinfunction "B_R1-B") (pintype "passive"))
      (node (ref "R25") (pin "2") (pinfunction "2_2") (pintype "passive"))
    )
    (net (code "62") (name "Net-(POT_MAIN_B-B)") (class "Default")
      (node (ref "POT_MAIN_") (pin "R2-B") (pinfunction "B_R2-B") (pintype "passive"))
      (node (ref "R26") (pin "2") (pinfunction "2_2") (pintype "passive"))
    )
    (net (code "63") (name "Net-(POT_MAIN_C-2)") (class "Default")
      (node (ref "J1") (pin "GND") (pinfunction "GND_GND") (pintype "bidirectional"))
      (node (ref "POT_MAIN_") (pin "P$2") (pinfunction "2_P$2") (pintype "bidirectional"))
    )
    (net (code "64") (name "Net-(PWR_LED-C)") (class "Default")
      (node (ref "PWR_LED") (pin "K") (pinfunction "C_K") (pintype "passive"))
      (node (ref "R31") (pin "2") (pinfunction "2_2") (pintype "passive"))
    )
    (net (code "65") (name "VCC") (class "Default")
      (node (ref "C21") (pin "1") (pinfunction "+_1") (pintype "passive"))
      (node (ref "C22") (pin "1") (pinfunction "+_1") (pintype "passive"))
      (node (ref "IC1") (pin "8") (pinfunction "V+_8") (pintype "power_in"))
      (node (ref "IC2") (pin "8") (pinfunction "V+_8") (pintype "power_in"))
      (node (ref "IC3") (pin "8") (pinfunction "V+_8") (pintype "power_in"))
      (node (ref "IC4") (pin "8") (pinfunction "V+_8") (pintype "power_in"))
      (node (ref "IC5") (pin "8") (pinfunction "V+_8") (pintype "power_in"))
      (node (ref "POT_MAIN_") (pin "P$1") (pinfunction "1_P$1") (pintype "bidirectional"))
      (node (ref "PWR_LED") (pin "A") (pinfunction "A_A") (pintype "passive"))
      (node (ref "U$2") (pin "PAD3") (pinfunction "IN_PAD3") (pintype "bidirectional"))
    )
  )
)
